# QCopterFC_LED_Sch.net
KiCad netlist of a schematic drawn in Altium Designer
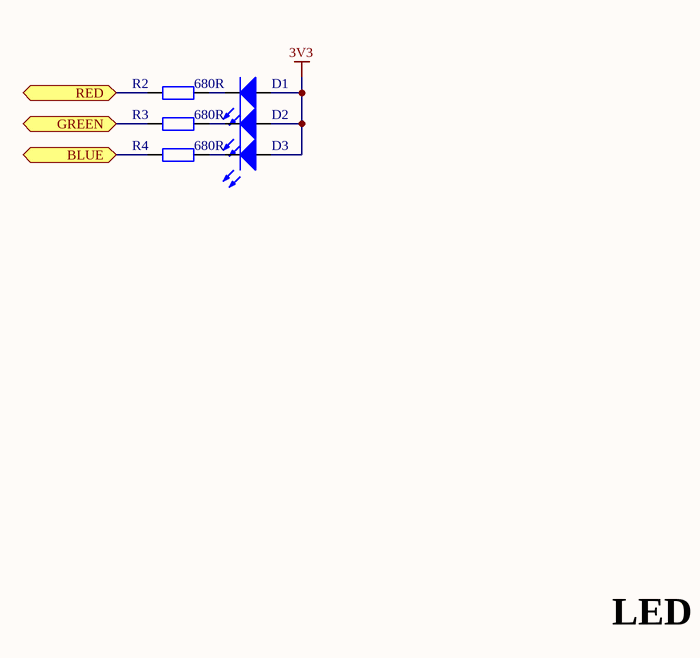
[diagram p0: QCopterFC_LED_Sch.SchDoc]

(export (version "E")
  (design (tool "Eeschema 10.0.6"))
  (components
    (comp (ref "D1")
      (value "LED_0603_RED")
      (footprint "PCB_Active:LED_0603_RED")
      (description "LED")
      (libsource (lib "SCH_Active") (part "LED_0603_RED"))
    )
    (comp (ref "D2")
      (value "LED_0603_GREEN")
      (footprint "PCB_Active:LED_0603_GREEN")
      (description "LED")
      (libsource (lib "SCH_Active") (part "LED_0603_GREEN"))
    )
    (comp (ref "D3")
      (value "LED_0603_BLUE")
      (footprint "PCB_Active:LED_0603_BLUE")
      (description "LED")
      (libsource (lib "SCH_Active") (part "LED_0603_BLUE"))
    )
    (comp (ref "R2")
      (value "680R")
      (footprint "PCB_Passive:RES_0603")
      (description "Resistor")
      (fields (field (name "Comment") "Res_0603"))
      (libsource (lib "SCH_Passive") (part "Res_0603"))
    )
    (comp (ref "R3")
      (value "680R")
      (footprint "PCB_Passive:RES_0603")
      (description "Resistor")
      (fields (field (name "Comment") "Res_0603"))
      (libsource (lib "SCH_Passive") (part "Res_0603"))
    )
    (comp (ref "R4")
      (value "680R")
      (footprint "PCB_Passive:RES_0603")
      (description "Resistor")
      (fields (field (name "Comment") "Res_0603"))
      (libsource (lib "SCH_Passive") (part "Res_0603"))
    )
  )
  (nets
    (net (code "1") (name "/BLUE") (class "Default")
      (node (ref "R4") (pin "1") (pinfunction "1_1") (pintype "passive"))
    )
    (net (code "2") (name "/GREEN") (class "Default")
      (node (ref "R3") (pin "1") (pinfunction "1_1") (pintype "passive"))
    )
    (net (code "3") (name "/RED") (class "Default")
      (node (ref "R2") (pin "1") (pinfunction "1_1") (pintype "passive"))
    )
    (net (code "4") (name "3V3") (class "Default")
      (node (ref "D1") (pin "1") (pinfunction "A_1") (pintype "passive"))
      (node (ref "D2") (pin "1") (pinfunction "A_1") (pintype "passive"))
      (node (ref "D3") (pin "1") (pinfunction "A_1") (pintype "passive"))
    )
    (net (code "5") (name "Net-(D1-K)") (class "Default")
      (node (ref "D1") (pin "2") (pinfunction "K_2") (pintype "passive"))
      (node (ref "R2") (pin "2") (pinfunction "2_2") (pintype "passive"))
    )
    (net (code "6") (name "Net-(D2-K)") (class "Default")
      (node (ref "D2") (pin "2") (pinfunction "K_2") (pintype "passive"))
      (node (ref "R3") (pin "2") (pinfunction "2_2") (pintype "passive"))
    )
    (net (code "7") (name "Net-(D3-K)") (class "Default")
      (node (ref "D3") (pin "2") (pinfunction "K_2") (pintype "passive"))
      (node (ref "R4") (pin "2") (pinfunction "2_2") (pintype "passive"))
    )
  )
)
